# SCH_Flight-Computer-V5_2024-08-08.net
KiCad netlist of a schematic drawn in EasyEDA
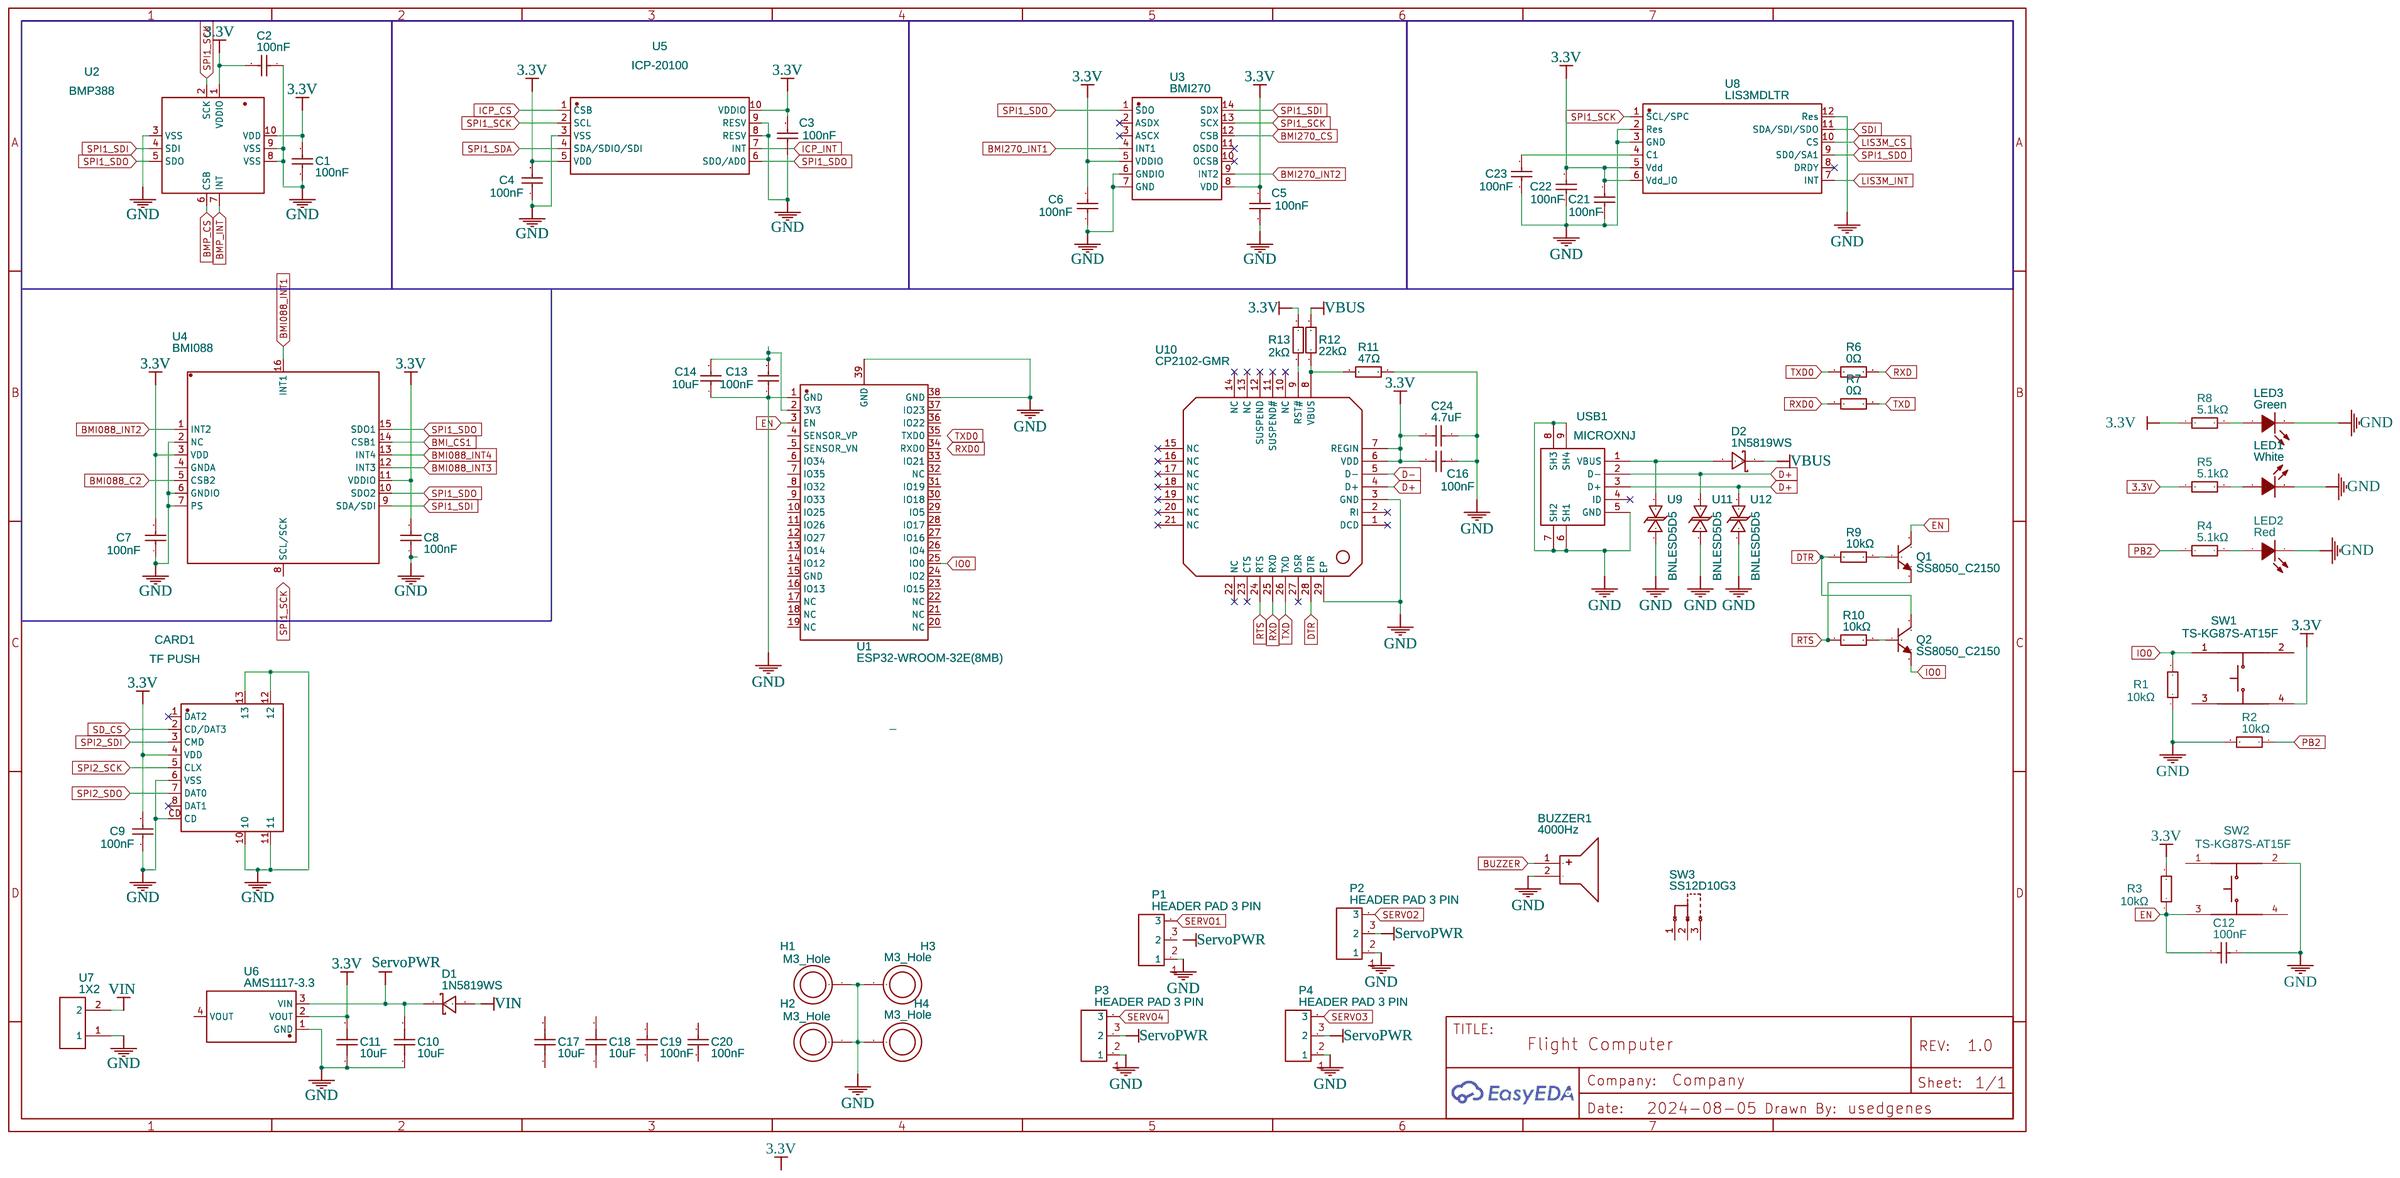
[diagram p0: schematic sheet]

(export (version "E")
  (design (tool "Eeschema 10.0.6"))
  (components
    (comp (ref "BUZZER1")
      (value "4000Hz")
      (fields
        (field (name "Manufacturer Part") "SKY-1475-0540-45P7.6")
        (field (name "Manufacturer") "S&S(海旭)")
      )
      (libsource (lib "") (part "SKY-1475-0540-45P7.6"))
    )
    (comp (ref "C1")
      (value "100nF")
      (fields
        (field (name "Manufacturer Part") "CL05B104KO5NNNC")
        (field (name "Manufacturer") "SAMSUNG(三星)")
      )
      (libsource (lib "") (part "CL05B104KO5NNNC_2"))
    )
    (comp (ref "C2")
      (value "100nF")
      (fields
        (field (name "Manufacturer Part") "CL05B104KO5NNNC")
        (field (name "Manufacturer") "SAMSUNG(三星)")
      )
      (libsource (lib "") (part "CL05B104KO5NNNC_3"))
    )
    (comp (ref "C3")
      (value "100nF")
      (fields
        (field (name "Manufacturer Part") "CL05B104KO5NNNC")
        (field (name "Manufacturer") "SAMSUNG(三星)")
      )
      (libsource (lib "") (part "CL05B104KO5NNNC_2"))
    )
    (comp (ref "C4")
      (value "100nF")
      (fields
        (field (name "Manufacturer Part") "CL05B104KO5NNNC")
        (field (name "Manufacturer") "SAMSUNG(三星)")
      )
      (libsource (lib "") (part "CL05B104KO5NNNC_2"))
    )
    (comp (ref "C5")
      (value "100nF")
      (fields
        (field (name "Manufacturer Part") "CL05B104KO5NNNC")
        (field (name "Manufacturer") "SAMSUNG(三星)")
      )
      (libsource (lib "") (part "CL05B104KO5NNNC_2"))
    )
    (comp (ref "C6")
      (value "100nF")
      (fields
        (field (name "Manufacturer Part") "CL05B104KO5NNNC")
        (field (name "Manufacturer") "SAMSUNG(三星)")
      )
      (libsource (lib "") (part "CL05B104KO5NNNC_2"))
    )
    (comp (ref "C7")
      (value "100nF")
      (fields
        (field (name "Manufacturer Part") "CL05B104KO5NNNC")
        (field (name "Manufacturer") "SAMSUNG(三星)")
      )
      (libsource (lib "") (part "CL05B104KO5NNNC_2"))
    )
    (comp (ref "C8")
      (value "100nF")
      (fields
        (field (name "Manufacturer Part") "CL05B104KO5NNNC")
        (field (name "Manufacturer") "SAMSUNG(三星)")
      )
      (libsource (lib "") (part "CL05B104KO5NNNC_2"))
    )
    (comp (ref "C9")
      (value "100nF")
      (fields
        (field (name "Manufacturer Part") "CL05B104KO5NNNC")
        (field (name "Manufacturer") "SAMSUNG(三星)")
      )
      (libsource (lib "") (part "CL05B104KO5NNNC_2"))
    )
    (comp (ref "C10")
      (value "10uF")
      (fields
        (field (name "Manufacturer Part") "CL10A106KP8NNNC")
        (field (name "Manufacturer") "SAMSUNG(三星)")
      )
      (libsource (lib "") (part "CL10A106KP8NNNC"))
    )
    (comp (ref "C11")
      (value "10uF")
      (fields
        (field (name "Manufacturer Part") "CL10A106KP8NNNC")
        (field (name "Manufacturer") "SAMSUNG(三星)")
      )
      (libsource (lib "") (part "CL10A106KP8NNNC"))
    )
    (comp (ref "C12")
      (value "100nF")
      (fields
        (field (name "Manufacturer Part") "CL05B104KO5NNNC")
        (field (name "Manufacturer") "SAMSUNG(三星)")
      )
      (libsource (lib "") (part "CL05B104KO5NNNC"))
    )
    (comp (ref "C13")
      (value "100nF")
      (fields
        (field (name "Manufacturer Part") "CL05B104KO5NNNC")
        (field (name "Manufacturer") "SAMSUNG(三星)")
      )
      (libsource (lib "") (part "CL05B104KO5NNNC_2"))
    )
    (comp (ref "C14")
      (value "10uF")
      (fields
        (field (name "Manufacturer Part") "CL05A106MQ5NUNC")
        (field (name "Manufacturer") "SAMSUNG(三星)")
      )
      (libsource (lib "") (part "CL05A106MQ5NUNC"))
    )
    (comp (ref "C16")
      (value "100nF")
      (fields
        (field (name "Manufacturer Part") "CL05B104KO5NNNC")
        (field (name "Manufacturer") "SAMSUNG(三星)")
      )
      (libsource (lib "") (part "CL05B104KO5NNNC"))
    )
    (comp (ref "C17")
      (value "10uF")
      (fields
        (field (name "Manufacturer Part") "CL10A106KP8NNNC")
        (field (name "Manufacturer") "SAMSUNG(三星)")
      )
      (libsource (lib "") (part "CL10A106KP8NNNC"))
    )
    (comp (ref "C18")
      (value "10uF")
      (fields
        (field (name "Manufacturer Part") "CL10A106KP8NNNC")
        (field (name "Manufacturer") "SAMSUNG(三星)")
      )
      (libsource (lib "") (part "CL10A106KP8NNNC"))
    )
    (comp (ref "C19")
      (value "100nF")
      (fields
        (field (name "Manufacturer Part") "CL05B104KO5NNNC")
        (field (name "Manufacturer") "SAMSUNG(三星)")
      )
      (libsource (lib "") (part "CL05B104KO5NNNC_2"))
    )
    (comp (ref "C20")
      (value "100nF")
      (fields
        (field (name "Manufacturer Part") "CL05B104KO5NNNC")
        (field (name "Manufacturer") "SAMSUNG(三星)")
      )
      (libsource (lib "") (part "CL05B104KO5NNNC_2"))
    )
    (comp (ref "C21")
      (value "100nF")
      (fields
        (field (name "Manufacturer Part") "CL05B104KO5NNNC")
        (field (name "Manufacturer") "SAMSUNG(三星)")
      )
      (libsource (lib "") (part "CL05B104KO5NNNC_1"))
    )
    (comp (ref "C22")
      (value "100nF")
      (fields
        (field (name "Manufacturer Part") "CL05B104KO5NNNC")
        (field (name "Manufacturer") "SAMSUNG(三星)")
      )
      (libsource (lib "") (part "CL05B104KO5NNNC_1"))
    )
    (comp (ref "C23")
      (value "100nF")
      (fields
        (field (name "Manufacturer Part") "CL05B104KO5NNNC")
        (field (name "Manufacturer") "SAMSUNG(三星)")
      )
      (libsource (lib "") (part "CL05B104KO5NNNC_1"))
    )
    (comp (ref "C24")
      (value "4.7uF")
      (fields
        (field (name "Manufacturer Part") "CL05A475MP5NRNC")
        (field (name "Manufacturer") "SAMSUNG(三星)")
      )
      (libsource (lib "") (part "CL05A475MP5NRNC"))
    )
    (comp (ref "CARD1")
      (value "TF PUSH")
      (fields (field (name "Manufacturer") "SHOU HAN(首韩)"))
      (libsource (lib "") (part "TF PUSH"))
    )
    (comp (ref "D1")
      (value "1N5819WS")
      (fields (field (name "Manufacturer") "Hottech(合科泰)"))
      (libsource (lib "") (part "1N5819WS_1"))
    )
    (comp (ref "D2")
      (value "1N5819WS")
      (fields (field (name "Manufacturer") "Hottech(合科泰)"))
      (libsource (lib "") (part "1N5819WS"))
    )
    (comp (ref "H1") (value "M3_Hole") (libsource (lib "") (part "3MM_HOLE_STICHING_VIAS_4MM_OUTER COPY")))
    (comp (ref "H2") (value "M3_Hole") (libsource (lib "") (part "3MM_HOLE_STICHING_VIAS_4MM_OUTER COPY")))
    (comp (ref "H3") (value "M3_Hole") (libsource (lib "") (part "3MM_HOLE_STICHING_VIAS_4MM_OUTER COPY_1")))
    (comp (ref "H4") (value "M3_Hole") (libsource (lib "") (part "3MM_HOLE_STICHING_VIAS_4MM_OUTER COPY_1")))
    (comp (ref "LED1")
      (value "White")
      (fields (field (name "Manufacturer Part") "KT-0603白灯") (field (name "Manufacturer") "KENTO"))
      (libsource (lib "") (part "0603White light_C2290"))
    )
    (comp (ref "LED2")
      (value "Red")
      (fields (field (name "Manufacturer Part") "KT-0603R") (field (name "Manufacturer") "KENTO"))
      (libsource (lib "") (part "KT-0603R"))
    )
    (comp (ref "LED3")
      (value "Green")
      (fields (field (name "Manufacturer Part") "KT-0805G") (field (name "Manufacturer") "KENTO"))
      (libsource (lib "") (part "0805G (Green)"))
    )
    (comp (ref "P1")
      (value "HEADER PAD 3 PIN")
      (fields
        (field (name "Manufacturer Part") "Female headerHDR1X8-2.54")
        (field (name "Manufacturer") "BOOMELE")
      )
      (libsource (lib "") (part "HEADER PAD 3 PIN"))
    )
    (comp (ref "P2")
      (value "HEADER PAD 3 PIN")
      (fields
        (field (name "Manufacturer Part") "Female headerHDR1X8-2.54")
        (field (name "Manufacturer") "BOOMELE")
      )
      (libsource (lib "") (part "HEADER PAD 3 PIN"))
    )
    (comp (ref "P3")
      (value "HEADER PAD 3 PIN")
      (fields
        (field (name "Manufacturer Part") "Female headerHDR1X8-2.54")
        (field (name "Manufacturer") "BOOMELE")
      )
      (libsource (lib "") (part "HEADER PAD 3 PIN"))
    )
    (comp (ref "P4")
      (value "HEADER PAD 3 PIN")
      (fields
        (field (name "Manufacturer Part") "Female headerHDR1X8-2.54")
        (field (name "Manufacturer") "BOOMELE")
      )
      (libsource (lib "") (part "HEADER PAD 3 PIN"))
    )
    (comp (ref "Q1")
      (value "SS8050_C2150")
      (fields (field (name "Manufacturer Part") "SS8050") (field (name "Manufacturer") "CJ(江苏长电/长晶)"))
      (libsource (lib "") (part "SS8050_C2150"))
    )
    (comp (ref "Q2")
      (value "SS8050_C2150")
      (fields (field (name "Manufacturer Part") "SS8050") (field (name "Manufacturer") "CJ(江苏长电/长晶)"))
      (libsource (lib "") (part "SS8050_C2150"))
    )
    (comp (ref "R1")
      (value "10kΩ")
      (fields
        (field (name "Manufacturer Part") "0603WAF1002T5E")
        (field (name "Manufacturer") "UNI-ROYAL(厚声)")
      )
      (libsource (lib "") (part "0603WAF1002T5E_1"))
    )
    (comp (ref "R2")
      (value "10kΩ")
      (fields
        (field (name "Manufacturer Part") "0603WAF1002T5E")
        (field (name "Manufacturer") "UNI-ROYAL(厚声)")
      )
      (libsource (lib "") (part "0603WAF1002T5E"))
    )
    (comp (ref "R3")
      (value "10kΩ")
      (fields
        (field (name "Manufacturer Part") "0603WAF1002T5E")
        (field (name "Manufacturer") "UNI-ROYAL(厚声)")
      )
      (libsource (lib "") (part "0603WAF1002T5E_1"))
    )
    (comp (ref "R4")
      (value "5.1kΩ")
      (fields
        (field (name "Manufacturer Part") "0402WGF5101TCE")
        (field (name "Manufacturer") "UNI-ROYAL(厚声)")
      )
      (libsource (lib "") (part "0402WGF5101TCE"))
    )
    (comp (ref "R5")
      (value "5.1kΩ")
      (fields
        (field (name "Manufacturer Part") "0402WGF5101TCE")
        (field (name "Manufacturer") "UNI-ROYAL(厚声)")
      )
      (libsource (lib "") (part "0402WGF5101TCE"))
    )
    (comp (ref "R6")
      (value "0Ω")
      (fields
        (field (name "Manufacturer Part") "1206W4F0000T5E")
        (field (name "Manufacturer") "UNI-ROYAL(厚声)")
      )
      (libsource (lib "") (part "1206W4F0000T5E"))
    )
    (comp (ref "R7")
      (value "0Ω")
      (fields
        (field (name "Manufacturer Part") "1206W4F0000T5E")
        (field (name "Manufacturer") "UNI-ROYAL(厚声)")
      )
      (libsource (lib "") (part "1206W4F0000T5E"))
    )
    (comp (ref "R8")
      (value "5.1kΩ")
      (fields
        (field (name "Manufacturer Part") "0402WGF5101TCE")
        (field (name "Manufacturer") "UNI-ROYAL(厚声)")
      )
      (libsource (lib "") (part "0402WGF5101TCE"))
    )
    (comp (ref "R9")
      (value "10kΩ")
      (fields
        (field (name "Manufacturer Part") "0603WAF1002T5E")
        (field (name "Manufacturer") "UNI-ROYAL(厚声)")
      )
      (libsource (lib "") (part "0603WAF1002T5E"))
    )
    (comp (ref "R10")
      (value "10kΩ")
      (fields
        (field (name "Manufacturer Part") "0603WAF1002T5E")
        (field (name "Manufacturer") "UNI-ROYAL(厚声)")
      )
      (libsource (lib "") (part "0603WAF1002T5E_2"))
    )
    (comp (ref "R11")
      (value "47Ω")
      (fields
        (field (name "Manufacturer Part") "0603WAF470JT5E")
        (field (name "Manufacturer") "UNI-ROYAL(厚声)")
      )
      (libsource (lib "") (part "0603WAF470JT5E"))
    )
    (comp (ref "R12")
      (value "22kΩ")
      (fields
        (field (name "Manufacturer Part") "0402WGF2202TCE")
        (field (name "Manufacturer") "UNI-ROYAL(厚声)")
      )
      (libsource (lib "") (part "0402WGF2202TCE"))
    )
    (comp (ref "R13")
      (value "2kΩ")
      (fields
        (field (name "Manufacturer Part") "0402WGF2001TCE")
        (field (name "Manufacturer") "UNI-ROYAL(厚声)")
      )
      (libsource (lib "") (part "0402WGF2001TCE"))
    )
    (comp (ref "SW1")
      (value "TS-KG87S-AT15F")
      (fields (field (name "Manufacturer") "HANBO(汉博)"))
      (libsource (lib "") (part "TS-KG87S-AT15F"))
    )
    (comp (ref "SW2")
      (value "TS-KG87S-AT15F")
      (fields (field (name "Manufacturer") "HANBO(汉博)"))
      (libsource (lib "") (part "TS-KG87S-AT15F"))
    )
    (comp (ref "SW3")
      (value "SS12D10G3")
      (fields (field (name "Manufacturer") "SHOU HAN(首韩)"))
      (libsource (lib "") (part "SS12D10G3"))
    )
    (comp (ref "U1")
      (value "ESP32-WROOM-32E(8MB)")
      (fields
        (field (name "Manufacturer Part") "ESP32-WROOM-32E-N8")
        (field (name "Manufacturer") "ESPRESSIF(乐鑫)")
      )
      (libsource (lib "") (part "ESP32-WROOM-32E(8MB)"))
    )
    (comp (ref "U2")
      (value "BMP388")
      (fields (field (name "Manufacturer") "Bosch(博世)"))
      (libsource (lib "") (part "BMP388"))
    )
    (comp (ref "U3")
      (value "BMI270")
      (fields (field (name "Manufacturer") "Bosch(博世)"))
      (libsource (lib "") (part "BMI270"))
    )
    (comp (ref "U4")
      (value "BMI088")
      (fields (field (name "Manufacturer") "Bosch(博世)"))
      (libsource (lib "") (part "BMI088"))
    )
    (comp (ref "U5")
      (value "ICP-20100")
      (fields (field (name "Manufacturer") "TDK"))
      (libsource (lib "") (part "ICP-20100"))
    )
    (comp (ref "U6")
      (value "AMS1117-3.3")
      (fields (field (name "Manufacturer") "AMS"))
      (libsource (lib "") (part "AMS1117-3.3"))
    )
    (comp (ref "U7") (value "1X2") (libsource (lib "") (part "1X2")))
    (comp (ref "U8")
      (value "LIS3MDLTR")
      (fields (field (name "Manufacturer") "ST(意法半导体)"))
      (libsource (lib "") (part "LIS3MDLTR"))
    )
    (comp (ref "U9")
      (value "BNLESD5D5")
      (fields
        (field (name "Manufacturer Part") "BNLESD5D5.0CT1G")
        (field (name "Manufacturer") "BORN(伯恩半导体)")
      )
      (libsource (lib "") (part "BNLESD5D5.0CT1G"))
    )
    (comp (ref "U10")
      (value "CP2102-GMR")
      (fields (field (name "Manufacturer") "SKYWORKS/SILICON LABS(芯科)"))
      (libsource (lib "") (part "CP2102-GMR"))
    )
    (comp (ref "U11")
      (value "BNLESD5D5")
      (fields
        (field (name "Manufacturer Part") "BNLESD5D5.0CT1G")
        (field (name "Manufacturer") "BORN(伯恩半导体)")
      )
      (libsource (lib "") (part "BNLESD5D5.0CT1G"))
    )
    (comp (ref "U12")
      (value "BNLESD5D5")
      (fields
        (field (name "Manufacturer Part") "BNLESD5D5.0CT1G")
        (field (name "Manufacturer") "BORN(伯恩半导体)")
      )
      (libsource (lib "") (part "BNLESD5D5.0CT1G"))
    )
    (comp (ref "USB1")
      (value "MICROXNJ")
      (fields (field (name "Manufacturer Part") "MicroXNJ") (field (name "Manufacturer") "SHOU HAN(首韩)"))
      (libsource (lib "") (part "MICROXNJ"))
    )
  )
  (nets
    (net (code "1") (name "3.3V") (class "Default")
      (node (ref "C1") (pin "2") (pinfunction "2_2") (pintype "input"))
      (node (ref "C11") (pin "2") (pinfunction "2_2") (pintype "unspecified"))
      (node (ref "C16") (pin "1") (pinfunction "1_1") (pintype "input"))
      (node (ref "C2") (pin "2") (pinfunction "2_2") (pintype "input"))
      (node (ref "C21") (pin "1") (pinfunction "1_1") (pintype "input"))
      (node (ref "C22") (pin "1") (pinfunction "1_1") (pintype "input"))
      (node (ref "C24") (pin "1") (pinfunction "1_1") (pintype "input"))
      (node (ref "C3") (pin "2") (pinfunction "2_2") (pintype "input"))
      (node (ref "C4") (pin "2") (pinfunction "2_2") (pintype "input"))
      (node (ref "C5") (pin "2") (pinfunction "2_2") (pintype "input"))
      (node (ref "C6") (pin "2") (pinfunction "2_2") (pintype "input"))
      (node (ref "C7") (pin "2") (pinfunction "2_2") (pintype "input"))
      (node (ref "C8") (pin "2") (pinfunction "2_2") (pintype "input"))
      (node (ref "C9") (pin "2") (pinfunction "2_2") (pintype "input"))
      (node (ref "CARD1") (pin "4") (pinfunction "VDD_4") (pintype "unspecified"))
      (node (ref "R13") (pin "1") (pinfunction "1_1") (pintype "input"))
      (node (ref "R3") (pin "2") (pinfunction "2_2") (pintype "input"))
      (node (ref "R5") (pin "1") (pinfunction "1_1") (pintype "input"))
      (node (ref "R8") (pin "1") (pinfunction "1_1") (pintype "input"))
      (node (ref "SW1") (pin "4") (pinfunction "4_4") (pintype "unspecified"))
      (node (ref "U10") (pin "6") (pinfunction "VDD_6") (pintype "unspecified"))
      (node (ref "U10") (pin "7") (pinfunction "REGIN_7") (pintype "unspecified"))
      (node (ref "U2") (pin "1") (pinfunction "VDDIO_1") (pintype "unspecified"))
      (node (ref "U2") (pin "10") (pinfunction "VDD_10") (pintype "unspecified"))
      (node (ref "U3") (pin "5") (pinfunction "VDDIO_5") (pintype "unspecified"))
      (node (ref "U3") (pin "8") (pinfunction "VDD_8") (pintype "unspecified"))
      (node (ref "U4") (pin "11") (pinfunction "VDDIO_11") (pintype "unspecified"))
      (node (ref "U4") (pin "3") (pinfunction "VDD_3") (pintype "unspecified"))
      (node (ref "U5") (pin "10") (pinfunction "VDDIO_10") (pintype "unspecified"))
      (node (ref "U5") (pin "5") (pinfunction "VDD_5") (pintype "unspecified"))
      (node (ref "U6") (pin "2") (pinfunction "VOUT_2") (pintype "unspecified"))
      (node (ref "U8") (pin "5") (pinfunction "Vdd_5") (pintype "unspecified"))
      (node (ref "U8") (pin "6") (pinfunction "Vdd_IO_6") (pintype "unspecified"))
    )
    (net (code "2") (name "BMI088_C2") (class "Default")
      (node (ref "U4") (pin "5") (pinfunction "CSB2_5") (pintype "unspecified"))
    )
    (net (code "3") (name "BMI088_INT1") (class "Default")
      (node (ref "U4") (pin "16") (pinfunction "INT1_16") (pintype "unspecified"))
    )
    (net (code "4") (name "BMI088_INT2") (class "Default")
      (node (ref "U4") (pin "1") (pinfunction "INT2_1") (pintype "unspecified"))
    )
    (net (code "5") (name "BMI088_INT3") (class "Default")
      (node (ref "U4") (pin "12") (pinfunction "INT3_12") (pintype "unspecified"))
    )
    (net (code "6") (name "BMI088_INT4") (class "Default")
      (node (ref "U4") (pin "13") (pinfunction "INT4_13") (pintype "unspecified"))
    )
    (net (code "7") (name "BMI270_CS") (class "Default")
      (node (ref "U3") (pin "12") (pinfunction "CSB_12") (pintype "unspecified"))
    )
    (net (code "8") (name "BMI270_INT1") (class "Default")
      (node (ref "U3") (pin "4") (pinfunction "INT1_4") (pintype "unspecified"))
    )
    (net (code "9") (name "BMI270_INT2") (class "Default")
      (node (ref "U3") (pin "9") (pinfunction "INT2_9") (pintype "unspecified"))
    )
    (net (code "10") (name "BMI_CS1") (class "Default")
      (node (ref "U4") (pin "14") (pinfunction "CSB1_14") (pintype "unspecified"))
    )
    (net (code "11") (name "BMP_CS") (class "Default")
      (node (ref "U2") (pin "6") (pinfunction "CSB_6") (pintype "unspecified"))
    )
    (net (code "12") (name "BMP_INT") (class "Default")
      (node (ref "U2") (pin "7") (pinfunction "INT_7") (pintype "unspecified"))
    )
    (net (code "13") (name "BUZZER") (class "Default")
      (node (ref "BUZZER1") (pin "1") (pinfunction "+_1") (pintype "unspecified"))
    )
    (net (code "14") (name "D+") (class "Default")
      (node (ref "U10") (pin "4") (pinfunction "D+_4") (pintype "unspecified"))
      (node (ref "U11") (pin "2") (pinfunction "2_2") (pintype "unspecified"))
      (node (ref "U12") (pin "2") (pinfunction "2_2") (pintype "unspecified"))
      (node (ref "USB1") (pin "2") (pinfunction "D-_2") (pintype "unspecified"))
      (node (ref "USB1") (pin "3") (pinfunction "D+_3") (pintype "unspecified"))
    )
    (net (code "15") (name "D-") (class "Default")
      (node (ref "U10") (pin "5") (pinfunction "D-_5") (pintype "unspecified"))
    )
    (net (code "16") (name "DTR") (class "Default")
      (node (ref "Q2") (pin "3") (pinfunction "C_3") (pintype "unspecified"))
      (node (ref "R9") (pin "2") (pinfunction "2_2") (pintype "input"))
      (node (ref "U10") (pin "28") (pinfunction "DTR_28") (pintype "unspecified"))
    )
    (net (code "17") (name "EN") (class "Default")
      (node (ref "C12") (pin "1") (pinfunction "1_1") (pintype "input"))
      (node (ref "Q1") (pin "3") (pinfunction "C_3") (pintype "unspecified"))
      (node (ref "R3") (pin "1") (pinfunction "1_1") (pintype "input"))
      (node (ref "SW2") (pin "3") (pinfunction "3_3") (pintype "unspecified"))
      (node (ref "U1") (pin "3") (pinfunction "EN_3") (pintype "unspecified"))
    )
    (net (code "18") (name "GND") (class "Default")
      (node (ref "BUZZER1") (pin "2") (pinfunction "-_2") (pintype "unspecified"))
      (node (ref "C1") (pin "1") (pinfunction "1_1") (pintype "input"))
      (node (ref "C10") (pin "1") (pinfunction "1_1") (pintype "unspecified"))
      (node (ref "C11") (pin "1") (pinfunction "1_1") (pintype "unspecified"))
      (node (ref "C12") (pin "2") (pinfunction "2_2") (pintype "input"))
      (node (ref "C13") (pin "1") (pinfunction "1_1") (pintype "input"))
      (node (ref "C14") (pin "1") (pinfunction "1_1") (pintype "input"))
      (node (ref "C16") (pin "2") (pinfunction "2_2") (pintype "input"))
      (node (ref "C2") (pin "1") (pinfunction "1_1") (pintype "input"))
      (node (ref "C21") (pin "2") (pinfunction "2_2") (pintype "input"))
      (node (ref "C22") (pin "2") (pinfunction "2_2") (pintype "input"))
      (node (ref "C23") (pin "2") (pinfunction "2_2") (pintype "input"))
      (node (ref "C24") (pin "2") (pinfunction "2_2") (pintype "input"))
      (node (ref "C3") (pin "1") (pinfunction "1_1") (pintype "input"))
      (node (ref "C4") (pin "1") (pinfunction "1_1") (pintype "input"))
      (node (ref "C5") (pin "1") (pinfunction "1_1") (pintype "input"))
      (node (ref "C6") (pin "1") (pinfunction "1_1") (pintype "input"))
      (node (ref "C7") (pin "1") (pinfunction "1_1") (pintype "input"))
      (node (ref "C8") (pin "1") (pinfunction "1_1") (pintype "input"))
      (node (ref "C9") (pin "1") (pinfunction "1_1") (pintype "input"))
      (node (ref "CARD1") (pin "10") (pinfunction "10_10") (pintype "unspecified"))
      (node (ref "CARD1") (pin "11") (pinfunction "11_11") (pintype "unspecified"))
      (node (ref "CARD1") (pin "12") (pinfunction "12_12") (pintype "unspecified"))
      (node (ref "CARD1") (pin "13") (pinfunction "13_13") (pintype "unspecified"))
      (node (ref "CARD1") (pin "6") (pinfunction "VSS_6") (pintype "unspecified"))
      (node (ref "CARD1") (pin "CD") (pinfunction "CD_CD") (pintype "unspecified"))
      (node (ref "H1") (pin "1") (pinfunction "1_1") (pintype "bidirectional"))
      (node (ref "H2") (pin "1") (pinfunction "1_1") (pintype "bidirectional"))
      (node (ref "H3") (pin "1") (pinfunction "1_1") (pintype "bidirectional"))
      (node (ref "H4") (pin "1") (pinfunction "1_1") (pintype "bidirectional"))
      (node (ref "LED1") (pin "2") (pinfunction "K_2") (pintype "unspecified"))
      (node (ref "LED2") (pin "1") (pinfunction "K_1") (pintype "unspecified"))
      (node (ref "LED3") (pin "2") (pinfunction "K_2") (pintype "unspecified"))
      (node (ref "P1") (pin "1") (pinfunction "1_1") (pintype "unspecified"))
      (node (ref "P2") (pin "1") (pinfunction "1_1") (pintype "unspecified"))
      (node (ref "P3") (pin "1") (pinfunction "1_1") (pintype "unspecified"))
      (node (ref "P4") (pin "1") (pinfunction "1_1") (pintype "unspecified"))
      (node (ref "R1") (pin "1") (pinfunction "1_1") (pintype "input"))
      (node (ref "R11") (pin "1") (pinfunction "1_1") (pintype "input"))
      (node (ref "R2") (pin "2") (pinfunction "2_2") (pintype "input"))
      (node (ref "SW2") (pin "2") (pinfunction "2_2") (pintype "unspecified"))
      (node (ref "U1") (pin "1") (pinfunction "GND_1") (pintype "unspecified"))
      (node (ref "U1") (pin "38") (pinfunction "GND_38") (pintype "unspecified"))
      (node (ref "U1") (pin "39") (pinfunction "GND_39") (pintype "unspecified"))
      (node (ref "U10") (pin "29") (pinfunction "EP_29") (pintype "unspecified"))
      (node (ref "U10") (pin "3") (pinfunction "GND_3") (pintype "unspecified"))
      (node (ref "U11") (pin "1") (pinfunction "1_1") (pintype "unspecified"))
      (node (ref "U12") (pin "1") (pinfunction "1_1") (pintype "unspecified"))
      (node (ref "U2") (pin "3") (pinfunction "VSS_3") (pintype "unspecified"))
      (node (ref "U2") (pin "8") (pinfunction "VSS_8") (pintype "unspecified"))
      (node (ref "U2") (pin "9") (pinfunction "VSS_9") (pintype "unspecified"))
      (node (ref "U3") (pin "6") (pinfunction "GNDIO_6") (pintype "unspecified"))
      (node (ref "U3") (pin "7") (pinfunction "GND_7") (pintype "unspecified"))
      (node (ref "U4") (pin "2") (pinfunction "NC_2") (pintype "unspecified"))
      (node (ref "U4") (pin "6") (pinfunction "GNDIO_6") (pintype "unspecified"))
      (node (ref "U4") (pin "7") (pinfunction "PS_7") (pintype "unspecified"))
      (node (ref "U5") (pin "3") (pinfunction "VSS_3") (pintype "unspecified"))
      (node (ref "U5") (pin "8") (pinfunction "RESV_8") (pintype "unspecified"))
      (node (ref "U5") (pin "9") (pinfunction "RESV_9") (pintype "unspecified"))
      (node (ref "U6") (pin "1") (pinfunction "GND_1") (pintype "unspecified"))
      (node (ref "U7") (pin "1") (pinfunction "1_1") (pintype "unspecified"))
      (node (ref "U8") (pin "12") (pinfunction "Res_12") (pintype "unspecified"))
      (node (ref "U8") (pin "2") (pinfunction "Res_2") (pintype "unspecified"))
      (node (ref "U8") (pin "3") (pinfunction "GND_3") (pintype "unspecified"))
      (node (ref "U9") (pin "1") (pinfunction "1_1") (pintype "unspecified"))
      (node (ref "USB1") (pin "5") (pinfunction "GND_5") (pintype "unspecified"))
      (node (ref "USB1") (pin "6") (pinfunction "SH1_6") (pintype "unspecified"))
      (node (ref "USB1") (pin "7") (pinfunction "SH2_7") (pintype "unspecified"))
      (node (ref "USB1") (pin "8") (pinfunction "SH3_8") (pintype "unspecified"))
      (node (ref "USB1") (pin "9") (pinfunction "SH4_9") (pintype "unspecified"))
    )
    (net (code "19") (name "ICP_CS") (class "Default")
      (node (ref "U5") (pin "1") (pinfunction "CSB_1") (pintype "unspecified"))
    )
    (net (code "20") (name "ICP_INT") (class "Default")
      (node (ref "U5") (pin "7") (pinfunction "INT_7") (pintype "unspecified"))
    )
    (net (code "21") (name "IO0") (class "Default")
      (node (ref "Q2") (pin "2") (pinfunction "E_2") (pintype "unspecified"))
      (node (ref "R1") (pin "2") (pinfunction "2_2") (pintype "input"))
      (node (ref "SW1") (pin "1") (pinfunction "1_1") (pintype "unspecified"))
      (node (ref "U1") (pin "25") (pinfunction "IO0_25") (pintype "unspecified"))
    )
    (net (code "22") (name "LIS3M_CS") (class "Default")
      (node (ref "U8") (pin "10") (pinfunction "CS_10") (pintype "unspecified"))
    )
    (net (code "23") (name "LIS3M_INT") (class "Default")
      (node (ref "U8") (pin "7") (pinfunction "INT_7") (pintype "unspecified"))
    )
    (net (code "24") (name "Net-(D2-A)") (class "Default")
      (node (ref "D2") (pin "2") (pinfunction "A_2") (pintype "unspecified"))
      (node (ref "U9") (pin "2") (pinfunction "2_2") (pintype "unspecified"))
      (node (ref "USB1") (pin "1") (pinfunction "VBUS_1") (pintype "unspecified"))
    )
    (net (code "25") (name "Net-(LED1-A)") (class "Default")
      (node (ref "LED1") (pin "1") (pinfunction "A_1") (pintype "unspecified"))
      (node (ref "R5") (pin "2") (pinfunction "2_2") (pintype "input"))
    )
    (net (code "26") (name "Net-(LED2-A)") (class "Default")
      (node (ref "LED2") (pin "2") (pinfunction "A_2") (pintype "unspecified"))
      (node (ref "R4") (pin "2") (pinfunction "2_2") (pintype "input"))
    )
    (net (code "27") (name "Net-(LED3-A)") (class "Default")
      (node (ref "LED3") (pin "1") (pinfunction "A_1") (pintype "unspecified"))
      (node (ref "R8") (pin "2") (pinfunction "2_2") (pintype "input"))
    )
    (net (code "28") (name "Net-(Q1-B)") (class "Default")
      (node (ref "Q1") (pin "1") (pinfunction "B_1") (pintype "unspecified"))
      (node (ref "R9") (pin "1") (pinfunction "1_1") (pintype "input"))
    )
    (net (code "29") (name "Net-(Q2-B)") (class "Default")
      (node (ref "Q2") (pin "1") (pinfunction "B_1") (pintype "unspecified"))
      (node (ref "R10") (pin "2") (pinfunction "2_2") (pintype "input"))
    )
    (net (code "30") (name "Net-(U1-3V3)") (class "Default")
      (node (ref "C13") (pin "2") (pinfunction "2_2") (pintype "input"))
      (node (ref "C14") (pin "2") (pinfunction "2_2") (pintype "input"))
      (node (ref "U1") (pin "2") (pinfunction "3V3_2") (pintype "unspecified"))
    )
    (net (code "31") (name "Net-(U8-C1)") (class "Default")
      (node (ref "C23") (pin "1") (pinfunction "1_1") (pintype "input"))
      (node (ref "U8") (pin "4") (pinfunction "C1_4") (pintype "unspecified"))
    )
    (net (code "32") (name "Net-(U10-RST#)") (class "Default")
      (node (ref "R13") (pin "2") (pinfunction "2_2") (pintype "input"))
      (node (ref "U10") (pin "9") (pinfunction "RST#_9") (pintype "unspecified"))
    )
    (net (code "33") (name "Net-(U10-VBUS)") (class "Default")
      (node (ref "R11") (pin "2") (pinfunction "2_2") (pintype "input"))
      (node (ref "R12") (pin "1") (pinfunction "1_1") (pintype "input"))
      (node (ref "U10") (pin "8") (pinfunction "VBUS_8") (pintype "unspecified"))
    )
    (net (code "34") (name "PB2") (class "Default")
      (node (ref "R2") (pin "1") (pinfunction "1_1") (pintype "input"))
      (node (ref "R4") (pin "1") (pinfunction "1_1") (pintype "input"))
    )
    (net (code "35") (name "RTS") (class "Default")
      (node (ref "Q1") (pin "2") (pinfunction "E_2") (pintype "unspecified"))
      (node (ref "R10") (pin "1") (pinfunction "1_1") (pintype "input"))
      (node (ref "U10") (pin "24") (pinfunction "RTS_24") (pintype "unspecified"))
    )
    (net (code "36") (name "RXD") (class "Default")
      (node (ref "R6") (pin "2") (pinfunction "2_2") (pintype "input"))
      (node (ref "U10") (pin "25") (pinfunction "RXD_25") (pintype "unspecified"))
    )
    (net (code "37") (name "RXD0") (class "Default")
      (node (ref "R7") (pin "1") (pinfunction "1_1") (pintype "input"))
    )
    (net (code "38") (name "SDI") (class "Default")
      (node (ref "U8") (pin "11") (pinfunction "SDA/SDI/SDO_11") (pintype "unspecified"))
    )
    (net (code "39") (name "SD_CS") (class "Default")
      (node (ref "CARD1") (pin "2") (pinfunction "CD/DAT3_2") (pintype "unspecified"))
    )
    (net (code "40") (name "SERVO1") (class "Default")
      (node (ref "P1") (pin "3") (pinfunction "3_3") (pintype "unspecified"))
    )
    (net (code "41") (name "SERVO2") (class "Default")
      (node (ref "P2") (pin "3") (pinfunction "3_3") (pintype "unspecified"))
    )
    (net (code "42") (name "SERVO3") (class "Default")
      (node (ref "P4") (pin "3") (pinfunction "3_3") (pintype "unspecified"))
    )
    (net (code "43") (name "SERVO4") (class "Default")
      (node (ref "P3") (pin "3") (pinfunction "3_3") (pintype "unspecified"))
    )
    (net (code "44") (name "SPI1_SCK") (class "Default")
      (node (ref "U2") (pin "2") (pinfunction "SCK_2") (pintype "unspecified"))
      (node (ref "U3") (pin "13") (pinfunction "SCX_13") (pintype "unspecified"))
      (node (ref "U5") (pin "2") (pinfunction "SCL_2") (pintype "unspecified"))
      (node (ref "U8") (pin "1") (pinfunction "SCL/SPC_1") (pintype "unspecified"))
    )
    (net (code "45") (name "SPI1_SDA") (class "Default")
      (node (ref "U5") (pin "4") (pinfunction "SDA/SDIO/SDI_4") (pintype "unspecified"))
    )
    (net (code "46") (name "SPI1_SDI") (class "Default")
      (node (ref "U2") (pin "4") (pinfunction "SDI_4") (pintype "unspecified"))
      (node (ref "U3") (pin "14") (pinfunction "SDX_14") (pintype "unspecified"))
      (node (ref "U4") (pin "9") (pinfunction "SDA/SDI_9") (pintype "unspecified"))
    )
    (net (code "47") (name "SPI1_SDO") (class "Default")
      (node (ref "U2") (pin "5") (pinfunction "SDO_5") (pintype "unspecified"))
      (node (ref "U3") (pin "1") (pinfunction "SDO_1") (pintype "unspecified"))
      (node (ref "U4") (pin "10") (pinfunction "SDO2_10") (pintype "unspecified"))
      (node (ref "U4") (pin "15") (pinfunction "SDO1_15") (pintype "unspecified"))
      (node (ref "U5") (pin "6") (pinfunction "SDO/AD0_6") (pintype "unspecified"))
      (node (ref "U8") (pin "9") (pinfunction "SD0/SA1_9") (pintype "unspecified"))
    )
    (net (code "48") (name "SPI2_SCK") (class "Default")
      (node (ref "CARD1") (pin "5") (pinfunction "CLX_5") (pintype "unspecified"))
    )
    (net (code "49") (name "SPI2_SDI") (class "Default")
      (node (ref "CARD1") (pin "3") (pinfunction "CMD_3") (pintype "unspecified"))
    )
    (net (code "50") (name "SPI2_SDO") (class "Default")
      (node (ref "CARD1") (pin "7") (pinfunction "DAT0_7") (pintype "unspecified"))
    )
    (net (code "51") (name "ServoPWR") (class "Default")
      (node (ref "C10") (pin "2") (pinfunction "2_2") (pintype "unspecified"))
      (node (ref "D1") (pin "1") (pinfunction "K_1") (pintype "unspecified"))
      (node (ref "P2") (pin "2") (pinfunction "2_2") (pintype "unspecified"))
      (node (ref "P3") (pin "2") (pinfunction "2_2") (pintype "unspecified"))
      (node (ref "P4") (pin "2") (pinfunction "2_2") (pintype "unspecified"))
      (node (ref "U6") (pin "3") (pinfunction "VIN_3") (pintype "unspecified"))
    )
    (net (code "52") (name "TXD") (class "Default")
      (node (ref "R7") (pin "2") (pinfunction "2_2") (pintype "input"))
      (node (ref "U10") (pin "26") (pinfunction "TXD_26") (pintype "unspecified"))
    )
    (net (code "53") (name "TXD0") (class "Default")
      (node (ref "R6") (pin "1") (pinfunction "1_1") (pintype "input"))
    )
    (net (code "54") (name "VBUS") (class "Default")
      (node (ref "D2") (pin "1") (pinfunction "K_1") (pintype "unspecified"))
      (node (ref "R12") (pin "2") (pinfunction "2_2") (pintype "input"))
    )
    (net (code "55") (name "VIN") (class "Default")
      (node (ref "D1") (pin "2") (pinfunction "A_2") (pintype "unspecified"))
      (node (ref "U7") (pin "2") (pinfunction "2_2") (pintype "unspecified"))
    )
    (net (code "56") (name "unconnected-(C17-Pad1)") (class "Default")
      (node (ref "C17") (pin "1") (pinfunction "1_1") (pintype "unspecified"))
    )
    (net (code "57") (name "unconnected-(C17-Pad2)") (class "Default")
      (node (ref "C17") (pin "2") (pinfunction "2_2") (pintype "unspecified"))
    )
    (net (code "58") (name "unconnected-(C18-Pad1)") (class "Default")
      (node (ref "C18") (pin "1") (pinfunction "1_1") (pintype "unspecified"))
    )
    (net (code "59") (name "unconnected-(C18-Pad2)") (class "Default")
      (node (ref "C18") (pin "2") (pinfunction "2_2") (pintype "unspecified"))
    )
    (net (code "60") (name "unconnected-(C19-Pad1)") (class "Default")
      (node (ref "C19") (pin "1") (pinfunction "1_1") (pintype "input"))
    )
    (net (code "61") (name "unconnected-(C19-Pad2)") (class "Default")
      (node (ref "C19") (pin "2") (pinfunction "2_2") (pintype "input"))
    )
    (net (code "62") (name "unconnected-(C20-Pad1)") (class "Default")
      (node (ref "C20") (pin "1") (pinfunction "1_1") (pintype "input"))
    )
    (net (code "63") (name "unconnected-(C20-Pad2)") (class "Default")
      (node (ref "C20") (pin "2") (pinfunction "2_2") (pintype "input"))
    )
    (net (code "64") (name "unconnected-(CARD1-DAT1-Pad8)") (class "Default")
      (node (ref "CARD1") (pin "8") (pinfunction "DAT1_8") (pintype "unspecified+no_connect"))
    )
    (net (code "65") (name "unconnected-(CARD1-DAT2-Pad1)") (class "Default")
      (node (ref "CARD1") (pin "1") (pinfunction "DAT2_1") (pintype "unspecified+no_connect"))
    )
    (net (code "66") (name "unconnected-(P1-Pad2)") (class "Default")
      (node (ref "P1") (pin "2") (pinfunction "2_2") (pintype "unspecified"))
    )
    (net (code "67") (name "unconnected-(SW1-Pad2)") (class "Default")
      (node (ref "SW1") (pin "2") (pinfunction "2_2") (pintype "unspecified"))
    )
    (net (code "68") (name "unconnected-(SW1-Pad3)") (class "Default")
      (node (ref "SW1") (pin "3") (pinfunction "3_3") (pintype "unspecified"))
    )
    (net (code "69") (name "unconnected-(SW2-Pad1)") (class "Default")
      (node (ref "SW2") (pin "1") (pinfunction "1_1") (pintype "unspecified"))
    )
    (net (code "70") (name "unconnected-(SW2-Pad4)") (class "Default")
      (node (ref "SW2") (pin "4") (pinfunction "4_4") (pintype "unspecified"))
    )
    (net (code "71") (name "unconnected-(SW3-Pad1)") (class "Default")
      (node (ref "SW3") (pin "1") (pinfunction "1_1") (pintype "unspecified"))
    )
    (net (code "72") (name "unconnected-(SW3-Pad2)") (class "Default")
      (node (ref "SW3") (pin "2") (pinfunction "2_2") (pintype "unspecified"))
    )
    (net (code "73") (name "unconnected-(SW3-Pad3)") (class "Default")
      (node (ref "SW3") (pin "3") (pinfunction "3_3") (pintype "unspecified"))
    )
    (net (code "74") (name "unconnected-(U1-GND-Pad15)") (class "Default")
      (node (ref "U1") (pin "15") (pinfunction "GND_15") (pintype "unspecified"))
    )
    (net (code "75") (name "unconnected-(U1-IO2-Pad24)") (class "Default")
      (node (ref "U1") (pin "24") (pinfunction "IO2_24") (pintype "unspecified"))
    )
    (net (code "76") (name "unconnected-(U1-IO4-Pad26)") (class "Default")
      (node (ref "U1") (pin "26") (pinfunction "IO4_26") (pintype "unspecified"))
    )
    (net (code "77") (name "unconnected-(U1-IO5-Pad29)") (class "Default")
      (node (ref "U1") (pin "29") (pinfunction "IO5_29") (pintype "unspecified"))
    )
    (net (code "78") (name "unconnected-(U1-IO12-Pad14)") (class "Default")
      (node (ref "U1") (pin "14") (pinfunction "IO12_14") (pintype "unspecified"))
    )
    (net (code "79") (name "unconnected-(U1-IO13-Pad16)") (class "Default")
      (node (ref "U1") (pin "16") (pinfunction "IO13_16") (pintype "unspecified"))
    )
    (net (code "80") (name "unconnected-(U1-IO14-Pad13)") (class "Default")
      (node (ref "U1") (pin "13") (pinfunction "IO14_13") (pintype "unspecified"))
    )
    (net (code "81") (name "unconnected-(U1-IO15-Pad23)") (class "Default")
      (node (ref "U1") (pin "23") (pinfunction "IO15_23") (pintype "unspecified"))
    )
    (net (code "82") (name "unconnected-(U1-IO16-Pad27)") (class "Default")
      (node (ref "U1") (pin "27") (pinfunction "IO16_27") (pintype "unspecified"))
    )
    (net (code "83") (name "unconnected-(U1-IO17-Pad28)") (class "Default")
      (node (ref "U1") (pin "28") (pinfunction "IO17_28") (pintype "unspecified"))
    )
    (net (code "84") (name "unconnected-(U1-IO18-Pad30)") (class "Default")
      (node (ref "U1") (pin "30") (pinfunction "IO18_30") (pintype "unspecified"))
    )
    (net (code "85") (name "unconnected-(U1-IO19-Pad31)") (class "Default")
      (node (ref "U1") (pin "31") (pinfunction "IO19_31") (pintype "unspecified"))
    )
    (net (code "86") (name "unconnected-(U1-IO21-Pad33)") (class "Default")
      (node (ref "U1") (pin "33") (pinfunction "IO21_33") (pintype "unspecified"))
    )
    (net (code "87") (name "unconnected-(U1-IO22-Pad36)") (class "Default")
      (node (ref "U1") (pin "36") (pinfunction "IO22_36") (pintype "unspecified"))
    )
    (net (code "88") (name "unconnected-(U1-IO23-Pad37)") (class "Default")
      (node (ref "U1") (pin "37") (pinfunction "IO23_37") (pintype "unspecified"))
    )
    (net (code "89") (name "unconnected-(U1-IO25-Pad10)") (class "Default")
      (node (ref "U1") (pin "10") (pinfunction "IO25_10") (pintype "unspecified"))
    )
    (net (code "90") (name "unconnected-(U1-IO26-Pad11)") (class "Default")
      (node (ref "U1") (pin "11") (pinfunction "IO26_11") (pintype "unspecified"))
    )
    (net (code "91") (name "unconnected-(U1-IO27-Pad12)") (class "Default")
      (node (ref "U1") (pin "12") (pinfunction "IO27_12") (pintype "unspecified"))
    )
    (net (code "92") (name "unconnected-(U1-IO32-Pad8)") (class "Default")
      (node (ref "U1") (pin "8") (pinfunction "IO32_8") (pintype "unspecified"))
    )
    (net (code "93") (name "unconnected-(U1-IO33-Pad9)") (class "Default")
      (node (ref "U1") (pin "9") (pinfunction "IO33_9") (pintype "unspecified"))
    )
    (net (code "94") (name "unconnected-(U1-IO34-Pad6)") (class "Default")
      (node (ref "U1") (pin "6") (pinfunction "IO34_6") (pintype "unspecified"))
    )
    (net (code "95") (name "unconnected-(U1-IO35-Pad7)") (class "Default")
      (node (ref "U1") (pin "7") (pinfunction "IO35_7") (pintype "unspecified"))
    )
    (net (code "96") (name "unconnected-(U1-NC-Pad17)") (class "Default")
      (node (ref "U1") (pin "17") (pinfunction "NC_17") (pintype "unspecified"))
    )
    (net (code "97") (name "unconnected-(U1-NC-Pad18)") (class "Default")
      (node (ref "U1") (pin "18") (pinfunction "NC_18") (pintype "unspecified"))
    )
    (net (code "98") (name "unconnected-(U1-NC-Pad19)") (class "Default")
      (node (ref "U1") (pin "19") (pinfunction "NC_19") (pintype "unspecified"))
    )
    (net (code "99") (name "unconnected-(U1-NC-Pad20)") (class "Default")
      (node (ref "U1") (pin "20") (pinfunction "NC_20") (pintype "unspecified"))
    )
    (net (code "100") (name "unconnected-(U1-NC-Pad21)") (class "Default")
      (node (ref "U1") (pin "21") (pinfunction "NC_21") (pintype "unspecified"))
    )
    (net (code "101") (name "unconnected-(U1-NC-Pad22)") (class "Default")
      (node (ref "U1") (pin "22") (pinfunction "NC_22") (pintype "unspecified"))
    )
    (net (code "102") (name "unconnected-(U1-NC-Pad32)") (class "Default")
      (node (ref "U1") (pin "32") (pinfunction "NC_32") (pintype "unspecified"))
    )
    (net (code "103") (name "unconnected-(U1-RXD0-Pad34)") (class "Default")
      (node (ref "U1") (pin "34") (pinfunction "RXD0_34") (pintype "unspecified"))
    )
    (net (code "104") (name "unconnected-(U1-SENSOR_VN-Pad5)") (class "Default")
      (node (ref "U1") (pin "5") (pinfunction "SENSOR_VN_5") (pintype "unspecified"))
    )
    (net (code "105") (name "unconnected-(U1-SENSOR_VP-Pad4)") (class "Default")
      (node (ref "U1") (pin "4") (pinfunction "SENSOR_VP_4") (pintype "unspecified"))
    )
    (net (code "106") (name "unconnected-(U1-TXD0-Pad35)") (class "Default")
      (node (ref "U1") (pin "35") (pinfunction "TXD0_35") (pintype "unspecified"))
    )
    (net (code "107") (name "unconnected-(U3-ASCX-Pad3)") (class "Default")
      (node (ref "U3") (pin "3") (pinfunction "ASCX_3") (pintype "unspecified+no_connect"))
    )
    (net (code "108") (name "unconnected-(U3-ASDX-Pad2)") (class "Default")
      (node (ref "U3") (pin "2") (pinfunction "ASDX_2") (pintype "unspecified+no_connect"))
    )
    (net (code "109") (name "unconnected-(U3-OCSB-Pad10)") (class "Default")
      (node (ref "U3") (pin "10") (pinfunction "OCSB_10") (pintype "unspecified+no_connect"))
    )
    (net (code "110") (name "unconnected-(U3-OSDO-Pad11)") (class "Default")
      (node (ref "U3") (pin "11") (pinfunction "OSDO_11") (pintype "unspecified+no_connect"))
    )
    (net (code "111") (name "unconnected-(U4-GNDA-Pad4)") (class "Default")
      (node (ref "U4") (pin "4") (pinfunction "GNDA_4") (pintype "unspecified"))
    )
    (net (code "112") (name "unconnected-(U4-SCL{slash}SCK-Pad8)") (class "Default")
      (node (ref "U4") (pin "8") (pinfunction "SCL/SCK_8") (pintype "unspecified"))
    )
    (net (code "113") (name "unconnected-(U6-VOUT-Pad4)") (class "Default")
      (node (ref "U6") (pin "4") (pinfunction "VOUT_4") (pintype "unspecified"))
    )
    (net (code "114") (name "unconnected-(U8-DRDY-Pad8)") (class "Default")
      (node (ref "U8") (pin "8") (pinfunction "DRDY_8") (pintype "unspecified+no_connect"))
    )
    (net (code "115") (name "unconnected-(U10-CTS-Pad23)") (class "Default")
      (node (ref "U10") (pin "23") (pinfunction "CTS_23") (pintype "unspecified+no_connect"))
    )
    (net (code "116") (name "unconnected-(U10-DCD-Pad1)") (class "Default")
      (node (ref "U10") (pin "1") (pinfunction "DCD_1") (pintype "unspecified+no_connect"))
    )
    (net (code "117") (name "unconnected-(U10-DSR-Pad27)") (class "Default")
      (node (ref "U10") (pin "27") (pinfunction "DSR_27") (pintype "unspecified+no_connect"))
    )
    (net (code "118") (name "unconnected-(U10-NC-Pad10)") (class "Default")
      (node (ref "U10") (pin "10") (pinfunction "NC_10") (pintype "unspecified+no_connect"))
    )
    (net (code "119") (name "unconnected-(U10-NC-Pad13)") (class "Default")
      (node (ref "U10") (pin "13") (pinfunction "NC_13") (pintype "unspecified+no_connect"))
    )
    (net (code "120") (name "unconnected-(U10-NC-Pad14)") (class "Default")
      (node (ref "U10") (pin "14") (pinfunction "NC_14") (pintype "unspecified+no_connect"))
    )
    (net (code "121") (name "unconnected-(U10-NC-Pad15)") (class "Default")
      (node (ref "U10") (pin "15") (pinfunction "NC_15") (pintype "unspecified+no_connect"))
    )
    (net (code "122") (name "unconnected-(U10-NC-Pad16)") (class "Default")
      (node (ref "U10") (pin "16") (pinfunction "NC_16") (pintype "unspecified+no_connect"))
    )
    (net (code "123") (name "unconnected-(U10-NC-Pad17)") (class "Default")
      (node (ref "U10") (pin "17") (pinfunction "NC_17") (pintype "unspecified+no_connect"))
    )
    (net (code "124") (name "unconnected-(U10-NC-Pad18)") (class "Default")
      (node (ref "U10") (pin "18") (pinfunction "NC_18") (pintype "unspecified+no_connect"))
    )
    (net (code "125") (name "unconnected-(U10-NC-Pad19)") (class "Default")
      (node (ref "U10") (pin "19") (pinfunction "NC_19") (pintype "unspecified+no_connect"))
    )
    (net (code "126") (name "unconnected-(U10-NC-Pad20)") (class "Default")
      (node (ref "U10") (pin "20") (pinfunction "NC_20") (pintype "unspecified+no_connect"))
    )
    (net (code "127") (name "unconnected-(U10-NC-Pad21)") (class "Default")
      (node (ref "U10") (pin "21") (pinfunction "NC_21") (pintype "unspecified+no_connect"))
    )
    (net (code "128") (name "unconnected-(U10-NC-Pad22)") (class "Default")
      (node (ref "U10") (pin "22") (pinfunction "NC_22") (pintype "unspecified+no_connect"))
    )
    (net (code "129") (name "unconnected-(U10-RI-Pad2)") (class "Default")
      (node (ref "U10") (pin "2") (pinfunction "RI_2") (pintype "unspecified+no_connect"))
    )
    (net (code "130") (name "unconnected-(U10-SUSPEND#-Pad11)") (class "Default")
      (node (ref "U10") (pin "11") (pinfunction "SUSPEND#_11") (pintype "unspecified+no_connect"))
    )
    (net (code "131") (name "unconnected-(U10-SUSPEND-Pad12)") (class "Default")
      (node (ref "U10") (pin "12") (pinfunction "SUSPEND_12") (pintype "unspecified+no_connect"))
    )
    (net (code "132") (name "unconnected-(USB1-ID-Pad4)") (class "Default")
      (node (ref "USB1") (pin "4") (pinfunction "ID_4") (pintype "unspecified+no_connect"))
    )
  )
)
